# Prometheus.net
KiCad netlist of a schematic drawn in Altium Designer
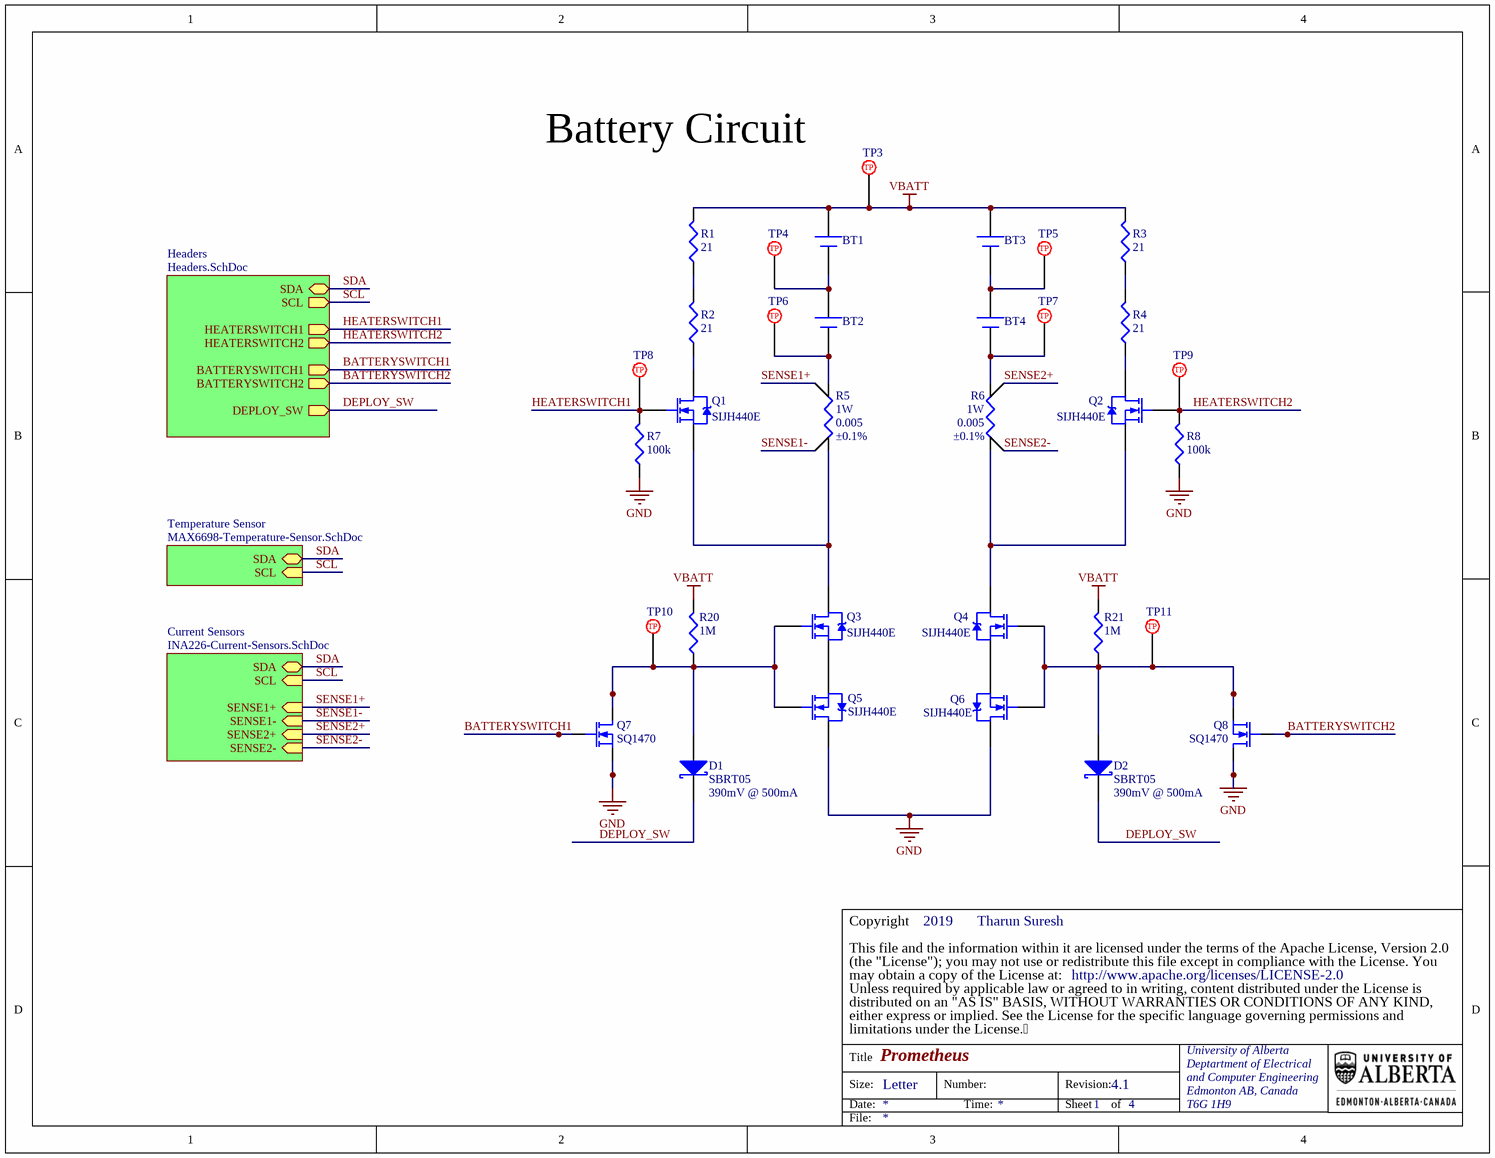
[diagram p0: Prometheus.SchDoc]

(export (version "E")
  (design (tool "Eeschema 10.0.6"))
  (components
    (comp (ref "BT1")
      (value "NCR18650PF")
      (footprint "ORB-PROTECTED18650")
      (description "18650 Battery-Panasonic Protected 2900mAh NCR18650PF Li-ion inside-10 Amp Dual Protection")
      (fields
        (field (name "PART NUMBER") "PBT-ORB-00001")
        (field (name "MANUFACTURER PART NUMBER") "BRB-2900")
        (field (name "PUBLISHER") "AlbertaSat")
      )
      (libsource (lib "Database") (part "Single-cell Battery"))
    )
    (comp (ref "BT2")
      (value "NCR18650PF")
      (footprint "ORB-PROTECTED18650")
      (description "18650 Battery-Panasonic Protected 2900mAh NCR18650PF Li-ion inside-10 Amp Dual Protection")
      (fields
        (field (name "PART NUMBER") "PBT-ORB-00001")
        (field (name "MANUFACTURER PART NUMBER") "BRB-2900")
        (field (name "PUBLISHER") "AlbertaSat")
      )
      (libsource (lib "Database") (part "Single-cell Battery"))
    )
    (comp (ref "BT3")
      (value "NCR18650PF")
      (footprint "ORB-PROTECTED18650")
      (description "18650 Battery-Panasonic Protected 2900mAh NCR18650PF Li-ion inside-10 Amp Dual Protection")
      (fields
        (field (name "PART NUMBER") "PBT-ORB-00001")
        (field (name "MANUFACTURER PART NUMBER") "BRB-2900")
        (field (name "PUBLISHER") "AlbertaSat")
      )
      (libsource (lib "Database") (part "Single-cell Battery"))
    )
    (comp (ref "BT4")
      (value "NCR18650PF")
      (footprint "ORB-PROTECTED18650")
      (description "18650 Battery-Panasonic Protected 2900mAh NCR18650PF Li-ion inside-10 Amp Dual Protection")
      (fields
        (field (name "PART NUMBER") "PBT-ORB-00001")
        (field (name "MANUFACTURER PART NUMBER") "BRB-2900")
        (field (name "PUBLISHER") "AlbertaSat")
      )
      (libsource (lib "Database") (part "Single-cell Battery"))
    )
    (comp (ref "D1")
      (value "SBRT05")
      (footprint "DIOD-X2-DFN1006-2")
      (description "SUPER BARRIER RECTIFIER X2-DFN10")
      (fields
        (field (name "PART NUMBER") "29")
        (field (name "MANUFACTURER PART NUMBER") "SBRT05U20LPS-7B")
        (field (name "VOLTAGE - FORWARD (MAX)") "390mV @ 500mA")
        (field (name "PUBLISHER") "Altium Limited")
      )
      (libsource (lib "Database") (part "D Schottky"))
    )
    (comp (ref "D2")
      (value "SBRT05")
      (footprint "DIOD-X2-DFN1006-2")
      (description "SUPER BARRIER RECTIFIER X2-DFN10")
      (fields
        (field (name "PART NUMBER") "29")
        (field (name "MANUFACTURER PART NUMBER") "SBRT05U20LPS-7B")
        (field (name "VOLTAGE - FORWARD (MAX)") "390mV @ 500mA")
        (field (name "PUBLISHER") "Altium Limited")
      )
      (libsource (lib "Database") (part "D Schottky"))
    )
    (comp (ref "Q1")
      (value "SIJH440E")
      (footprint "VSH-POWERPAK8X8L")
      (description "NMOS-2")
      (fields
        (field (name "PART NUMBER") "PQ-VSH-00270")
        (field (name "MANUFACTURER PART NUMBER") "SIJH440E-T1-GE3")
        (field (name "PUBLISHER") "AlbertaSat")
      )
      (libsource (lib "Database") (part "NMOS-2"))
    )
    (comp (ref "Q2")
      (value "SIJH440E")
      (footprint "VSH-POWERPAK8X8L")
      (description "NMOS-2")
      (fields
        (field (name "PART NUMBER") "PQ-VSH-00270")
        (field (name "MANUFACTURER PART NUMBER") "SIJH440E-T1-GE3")
        (field (name "PUBLISHER") "AlbertaSat")
      )
      (libsource (lib "Database") (part "NMOS-2"))
    )
    (comp (ref "Q3")
      (value "SIJH440E")
      (footprint "VSH-POWERPAK8X8L")
      (description "NMOS-2")
      (fields
        (field (name "PART NUMBER") "PQ-VSH-00270")
        (field (name "MANUFACTURER PART NUMBER") "SIJH440E-T1-GE3")
        (field (name "PUBLISHER") "AlbertaSat")
      )
      (libsource (lib "Database") (part "NMOS-2"))
    )
    (comp (ref "Q4")
      (value "SIJH440E")
      (footprint "VSH-POWERPAK8X8L")
      (description "NMOS-2")
      (fields
        (field (name "PART NUMBER") "PQ-VSH-00270")
        (field (name "MANUFACTURER PART NUMBER") "SIJH440E-T1-GE3")
        (field (name "PUBLISHER") "AlbertaSat")
      )
      (libsource (lib "Database") (part "NMOS-2"))
    )
    (comp (ref "Q5")
      (value "SIJH440E")
      (footprint "VSH-POWERPAK8X8L")
      (description "NMOS-2")
      (fields
        (field (name "PART NUMBER") "PQ-VSH-00270")
        (field (name "MANUFACTURER PART NUMBER") "SIJH440E-T1-GE3")
        (field (name "PUBLISHER") "AlbertaSat")
      )
      (libsource (lib "Database") (part "NMOS-2"))
    )
    (comp (ref "Q6")
      (value "SIJH440E")
      (footprint "VSH-POWERPAK8X8L")
      (description "NMOS-2")
      (fields
        (field (name "PART NUMBER") "PQ-VSH-00270")
        (field (name "MANUFACTURER PART NUMBER") "SIJH440E-T1-GE3")
        (field (name "PUBLISHER") "AlbertaSat")
      )
      (libsource (lib "Database") (part "NMOS-2"))
    )
    (comp (ref "Q7")
      (value "SQ1470")
      (footprint "VSH-SQ1470AEH")
      (description "MOSFET N-CH 30V 2.8A SC70")
      (fields
        (field (name "PART NUMBER") "PQ-VSH-00227")
        (field (name "MANUFACTURER PART NUMBER") "SQ1470AEH-T1_GE3")
        (field (name "PUBLISHER") "AlbertaSat")
      )
      (libsource (lib "Database") (part "MOSFET-N"))
    )
    (comp (ref "Q8")
      (value "SQ1470")
      (footprint "VSH-SQ1470AEH")
      (description "MOSFET N-CH 30V 2.8A SC70")
      (fields
        (field (name "PART NUMBER") "PQ-VSH-00227")
        (field (name "MANUFACTURER PART NUMBER") "SQ1470AEH-T1_GE3")
        (field (name "PUBLISHER") "AlbertaSat")
      )
      (libsource (lib "Database") (part "MOSFET-N"))
    )
    (comp (ref "R1")
      (value "21")
      (footprint "VSH-CPF1")
      (description "21 Ohms ±1% 1W Through Hole Resistor Axial Flame Proof, Moisture Resistant, Safety Metal Film")
      (fields
        (field (name "PART NUMBER") "PR-VSH-00269")
        (field (name "MANUFACTURER PART NUMBER") "CPF121R000FKEE6")
        (field (name "PUBLISHER") "AlbertaSat")
      )
      (libsource (lib "Database") (part "Res3"))
    )
    (comp (ref "R2")
      (value "21")
      (footprint "VSH-CPF1")
      (description "21 Ohms ±1% 1W Through Hole Resistor Axial Flame Proof, Moisture Resistant, Safety Metal Film")
      (fields
        (field (name "PART NUMBER") "PR-VSH-00269")
        (field (name "MANUFACTURER PART NUMBER") "CPF121R000FKEE6")
        (field (name "PUBLISHER") "AlbertaSat")
      )
      (libsource (lib "Database") (part "Res3"))
    )
    (comp (ref "R3")
      (value "21")
      (footprint "VSH-CPF1")
      (description "21 Ohms ±1% 1W Through Hole Resistor Axial Flame Proof, Moisture Resistant, Safety Metal Film")
      (fields
        (field (name "PART NUMBER") "PR-VSH-00269")
        (field (name "MANUFACTURER PART NUMBER") "CPF121R000FKEE6")
        (field (name "PUBLISHER") "AlbertaSat")
      )
      (libsource (lib "Database") (part "Res3"))
    )
    (comp (ref "R4")
      (value "21")
      (footprint "VSH-CPF1")
      (description "21 Ohms ±1% 1W Through Hole Resistor Axial Flame Proof, Moisture Resistant, Safety Metal Film")
      (fields
        (field (name "PART NUMBER") "PR-VSH-00269")
        (field (name "MANUFACTURER PART NUMBER") "CPF121R000FKEE6")
        (field (name "PUBLISHER") "AlbertaSat")
      )
      (libsource (lib "Database") (part "Res3"))
    )
    (comp (ref "R5")
      (value "0.005")
      (footprint "VSH-2512R4B")
      (description "RES SMD 0.005 OHM 0.1% 1W 2512")
      (fields
        (field (name "POWER - RATED") "1W")
        (field (name "TOLERANCE") "±0.1%")
        (field (name "PART NUMBER") "PR-VSH-00234")
        (field (name "MANUFACTURER PART NUMBER") "Y14870R00500B9R")
        (field (name "PUBLISHER") "AlbertaSat")
      )
      (libsource (lib "Database") (part "Res Sense"))
    )
    (comp (ref "R6")
      (value "0.005")
      (footprint "VSH-2512R4B")
      (description "RES SMD 0.005 OHM 0.1% 1W 2512")
      (fields
        (field (name "POWER - RATED") "1W")
        (field (name "TOLERANCE") "±0.1%")
        (field (name "PART NUMBER") "PR-VSH-00234")
        (field (name "MANUFACTURER PART NUMBER") "Y14870R00500B9R")
        (field (name "PUBLISHER") "AlbertaSat")
      )
      (libsource (lib "Database") (part "Res Sense"))
    )
    (comp (ref "R7")
      (value "100k")
      (footprint "PANA-ERJ6EN")
      (description "RES SMD 100K OHM 1% 1/8W 0805")
      (fields
        (field (name "PART NUMBER") "18749")
        (field (name "MANUFACTURER PART NUMBER") "ERJ-6ENF1003V")
        (field (name "PUBLISHER") "Altium Limited")
      )
      (libsource (lib "Database") (part "Res3"))
    )
    (comp (ref "R8")
      (value "100k")
      (footprint "PANA-ERJ6EN")
      (description "RES SMD 100K OHM 1% 1/8W 0805")
      (fields
        (field (name "PART NUMBER") "18749")
        (field (name "MANUFACTURER PART NUMBER") "ERJ-6ENF1003V")
        (field (name "PUBLISHER") "Altium Limited")
      )
      (libsource (lib "Database") (part "Res3"))
    )
    (comp (ref "R20")
      (value "1M")
      (footprint "PANA-ERJ6EN")
      (description "RES SMD 1M OHM 1% 1/8W 0805")
      (fields
        (field (name "PART NUMBER") "19707")
        (field (name "MANUFACTURER PART NUMBER") "ERJ-6ENF1004V")
        (field (name "PUBLISHER") "Altium Limited")
      )
      (libsource (lib "Database") (part "Res3"))
    )
    (comp (ref "R21")
      (value "1M")
      (footprint "PANA-ERJ6EN")
      (description "RES SMD 1M OHM 1% 1/8W 0805")
      (fields
        (field (name "PART NUMBER") "19707")
        (field (name "MANUFACTURER PART NUMBER") "ERJ-6ENF1004V")
        (field (name "PUBLISHER") "Altium Limited")
      )
      (libsource (lib "Database") (part "Res3"))
    )
    (comp (ref "TP3")
      (value "5017")
      (footprint "KS-5017")
      (description "PC TEST POINT MINI SMD")
      (fields (field (name "PART NUMBER") "PTP-KS-00001") (field (name "PUBLISHER") "AlbertaSat"))
      (libsource (lib "Database") (part "5017"))
    )
    (comp (ref "TP4")
      (value "5017")
      (footprint "KS-5017")
      (description "PC TEST POINT MINI SMD")
      (fields (field (name "PART NUMBER") "PTP-KS-00001") (field (name "PUBLISHER") "AlbertaSat"))
      (libsource (lib "Database") (part "5017"))
    )
    (comp (ref "TP5")
      (value "5017")
      (footprint "KS-5017")
      (description "PC TEST POINT MINI SMD")
      (fields (field (name "PART NUMBER") "PTP-KS-00001") (field (name "PUBLISHER") "AlbertaSat"))
      (libsource (lib "Database") (part "5017"))
    )
    (comp (ref "TP6")
      (value "5017")
      (footprint "KS-5017")
      (description "PC TEST POINT MINI SMD")
      (fields (field (name "PART NUMBER") "PTP-KS-00001") (field (name "PUBLISHER") "AlbertaSat"))
      (libsource (lib "Database") (part "5017"))
    )
    (comp (ref "TP7")
      (value "5017")
      (footprint "KS-5017")
      (description "PC TEST POINT MINI SMD")
      (fields (field (name "PART NUMBER") "PTP-KS-00001") (field (name "PUBLISHER") "AlbertaSat"))
      (libsource (lib "Database") (part "5017"))
    )
    (comp (ref "TP8")
      (value "5017")
      (footprint "KS-5017")
      (description "PC TEST POINT MINI SMD")
      (fields (field (name "PART NUMBER") "PTP-KS-00001") (field (name "PUBLISHER") "AlbertaSat"))
      (libsource (lib "Database") (part "5017"))
    )
    (comp (ref "TP9")
      (value "5017")
      (footprint "KS-5017")
      (description "PC TEST POINT MINI SMD")
      (fields (field (name "PART NUMBER") "PTP-KS-00001") (field (name "PUBLISHER") "AlbertaSat"))
      (libsource (lib "Database") (part "5017"))
    )
    (comp (ref "TP10")
      (value "5017")
      (footprint "KS-5017")
      (description "PC TEST POINT MINI SMD")
      (fields (field (name "PART NUMBER") "PTP-KS-00001") (field (name "PUBLISHER") "AlbertaSat"))
      (libsource (lib "Database") (part "5017"))
    )
    (comp (ref "TP11")
      (value "5017")
      (footprint "KS-5017")
      (description "PC TEST POINT MINI SMD")
      (fields (field (name "PART NUMBER") "PTP-KS-00001") (field (name "PUBLISHER") "AlbertaSat"))
      (libsource (lib "Database") (part "5017"))
    )
  )
  (nets
    (net (code "1") (name "/BATTERYSWITCH1") (class "Default")
      (node (ref "Q7") (pin "2") (pinfunction "G_2") (pintype "passive"))
    )
    (net (code "2") (name "/BATTERYSWITCH2") (class "Default")
      (node (ref "Q8") (pin "2") (pinfunction "G_2") (pintype "passive"))
    )
    (net (code "3") (name "/DEPLOY_SW") (class "Default")
      (node (ref "D1") (pin "2") (pinfunction "K_2") (pintype "passive"))
      (node (ref "D2") (pin "2") (pinfunction "K_2") (pintype "passive"))
    )
    (net (code "4") (name "/HEATERSWITCH1") (class "Default")
      (node (ref "Q1") (pin "1") (pinfunction "G_1") (pintype "passive"))
      (node (ref "R7") (pin "2") (pinfunction "2_2") (pintype "passive"))
      (node (ref "TP8") (pin "1") (pinfunction "1_1") (pintype "passive"))
    )
    (net (code "5") (name "/HEATERSWITCH2") (class "Default")
      (node (ref "Q2") (pin "1") (pinfunction "G_1") (pintype "passive"))
      (node (ref "R8") (pin "2") (pinfunction "2_2") (pintype "passive"))
      (node (ref "TP9") (pin "1") (pinfunction "1_1") (pintype "passive"))
    )
    (net (code "8") (name "/SENSE1+") (class "Default")
      (node (ref "R5") (pin "3") (pinfunction "S2_3") (pintype "passive"))
    )
    (net (code "9") (name "/SENSE1-") (class "Default")
      (node (ref "R5") (pin "4") (pinfunction "S1_4") (pintype "passive"))
    )
    (net (code "10") (name "/SENSE2+") (class "Default")
      (node (ref "R6") (pin "4") (pinfunction "S1_4") (pintype "passive"))
    )
    (net (code "11") (name "/SENSE2-") (class "Default")
      (node (ref "R6") (pin "3") (pinfunction "S2_3") (pintype "passive"))
    )
    (net (code "12") (name "GND") (class "Default")
      (node (ref "Q5") (pin "2") (pinfunction "D_2") (pintype "passive"))
      (node (ref "Q6") (pin "2") (pinfunction "D_2") (pintype "passive"))
      (node (ref "Q7") (pin "3") (pinfunction "S_3") (pintype "passive"))
      (node (ref "Q8") (pin "1") (pinfunction "D_1") (pintype "passive"))
      (node (ref "R7") (pin "1") (pinfunction "1_1") (pintype "passive"))
      (node (ref "R8") (pin "1") (pinfunction "1_1") (pintype "passive"))
    )
    (net (code "13") (name "Net-(BT1--)") (class "Default")
      (node (ref "BT1") (pin "2") (pinfunction "-_2") (pintype "passive"))
      (node (ref "BT2") (pin "1") (pinfunction "+_1") (pintype "passive"))
      (node (ref "TP4") (pin "1") (pinfunction "1_1") (pintype "passive"))
    )
    (net (code "14") (name "Net-(BT2--)") (class "Default")
      (node (ref "BT2") (pin "2") (pinfunction "-_2") (pintype "passive"))
      (node (ref "R5") (pin "2") (pinfunction "I2_2") (pintype "passive"))
      (node (ref "TP6") (pin "1") (pinfunction "1_1") (pintype "passive"))
    )
    (net (code "15") (name "Net-(BT3--)") (class "Default")
      (node (ref "BT3") (pin "2") (pinfunction "-_2") (pintype "passive"))
      (node (ref "BT4") (pin "1") (pinfunction "+_1") (pintype "passive"))
      (node (ref "TP5") (pin "1") (pinfunction "1_1") (pintype "passive"))
    )
    (net (code "16") (name "Net-(BT4--)") (class "Default")
      (node (ref "BT4") (pin "2") (pinfunction "-_2") (pintype "passive"))
      (node (ref "R6") (pin "1") (pinfunction "I1_1") (pintype "passive"))
      (node (ref "TP7") (pin "1") (pinfunction "1_1") (pintype "passive"))
    )
    (net (code "17") (name "Net-(D1-A)") (class "Default")
      (node (ref "D1") (pin "1") (pinfunction "A_1") (pintype "passive"))
      (node (ref "Q3") (pin "1") (pinfunction "G_1") (pintype "passive"))
      (node (ref "Q5") (pin "1") (pinfunction "G_1") (pintype "passive"))
      (node (ref "Q7") (pin "1") (pinfunction "D_1") (pintype "passive"))
      (node (ref "R20") (pin "1") (pinfunction "1_1") (pintype "passive"))
      (node (ref "TP10") (pin "1") (pinfunction "1_1") (pintype "passive"))
    )
    (net (code "18") (name "Net-(D2-A)") (class "Default")
      (node (ref "D2") (pin "1") (pinfunction "A_1") (pintype "passive"))
      (node (ref "Q4") (pin "1") (pinfunction "G_1") (pintype "passive"))
      (node (ref "Q6") (pin "1") (pinfunction "G_1") (pintype "passive"))
      (node (ref "Q8") (pin "3") (pinfunction "S_3") (pintype "passive"))
      (node (ref "R21") (pin "1") (pinfunction "1_1") (pintype "passive"))
      (node (ref "TP11") (pin "1") (pinfunction "1_1") (pintype "passive"))
    )
    (net (code "19") (name "Net-(Q1-D)") (class "Default")
      (node (ref "Q1") (pin "2") (pinfunction "D_2") (pintype "passive"))
      (node (ref "R2") (pin "1") (pinfunction "1_1") (pintype "passive"))
    )
    (net (code "20") (name "Net-(Q1-S)") (class "Default")
      (node (ref "Q1") (pin "3") (pinfunction "S_3") (pintype "passive"))
      (node (ref "Q3") (pin "2") (pinfunction "D_2") (pintype "passive"))
      (node (ref "R5") (pin "1") (pinfunction "I1_1") (pintype "passive"))
    )
    (net (code "21") (name "Net-(Q2-D)") (class "Default")
      (node (ref "Q2") (pin "2") (pinfunction "D_2") (pintype "passive"))
      (node (ref "R4") (pin "1") (pinfunction "1_1") (pintype "passive"))
    )
    (net (code "22") (name "Net-(Q2-S)") (class "Default")
      (node (ref "Q2") (pin "3") (pinfunction "S_3") (pintype "passive"))
      (node (ref "Q4") (pin "2") (pinfunction "D_2") (pintype "passive"))
      (node (ref "R6") (pin "2") (pinfunction "I2_2") (pintype "passive"))
    )
    (net (code "23") (name "Net-(Q3-S)") (class "Default")
      (node (ref "Q3") (pin "3") (pinfunction "S_3") (pintype "passive"))
      (node (ref "Q5") (pin "3") (pinfunction "S_3") (pintype "passive"))
    )
    (net (code "24") (name "Net-(Q4-S)") (class "Default")
      (node (ref "Q4") (pin "3") (pinfunction "S_3") (pintype "passive"))
      (node (ref "Q6") (pin "3") (pinfunction "S_3") (pintype "passive"))
    )
    (net (code "25") (name "Net-(R1-Pad1)") (class "Default")
      (node (ref "R1") (pin "1") (pinfunction "1_1") (pintype "passive"))
      (node (ref "R2") (pin "2") (pinfunction "2_2") (pintype "passive"))
    )
    (net (code "26") (name "Net-(R3-Pad1)") (class "Default")
      (node (ref "R3") (pin "1") (pinfunction "1_1") (pintype "passive"))
      (node (ref "R4") (pin "2") (pinfunction "2_2") (pintype "passive"))
    )
    (net (code "27") (name "VBATT") (class "Default")
      (node (ref "BT1") (pin "1") (pinfunction "+_1") (pintype "passive"))
      (node (ref "BT3") (pin "1") (pinfunction "+_1") (pintype "passive"))
      (node (ref "R1") (pin "2") (pinfunction "2_2") (pintype "passive"))
      (node (ref "R20") (pin "2") (pinfunction "2_2") (pintype "passive"))
      (node (ref "R21") (pin "2") (pinfunction "2_2") (pintype "passive"))
      (node (ref "R3") (pin "2") (pinfunction "2_2") (pintype "passive"))
      (node (ref "TP3") (pin "1") (pinfunction "1_1") (pintype "passive"))
    )
  )
)
